# logger_SMD_0603_v1.net
KiCad netlist of a schematic drawn in EAGLE
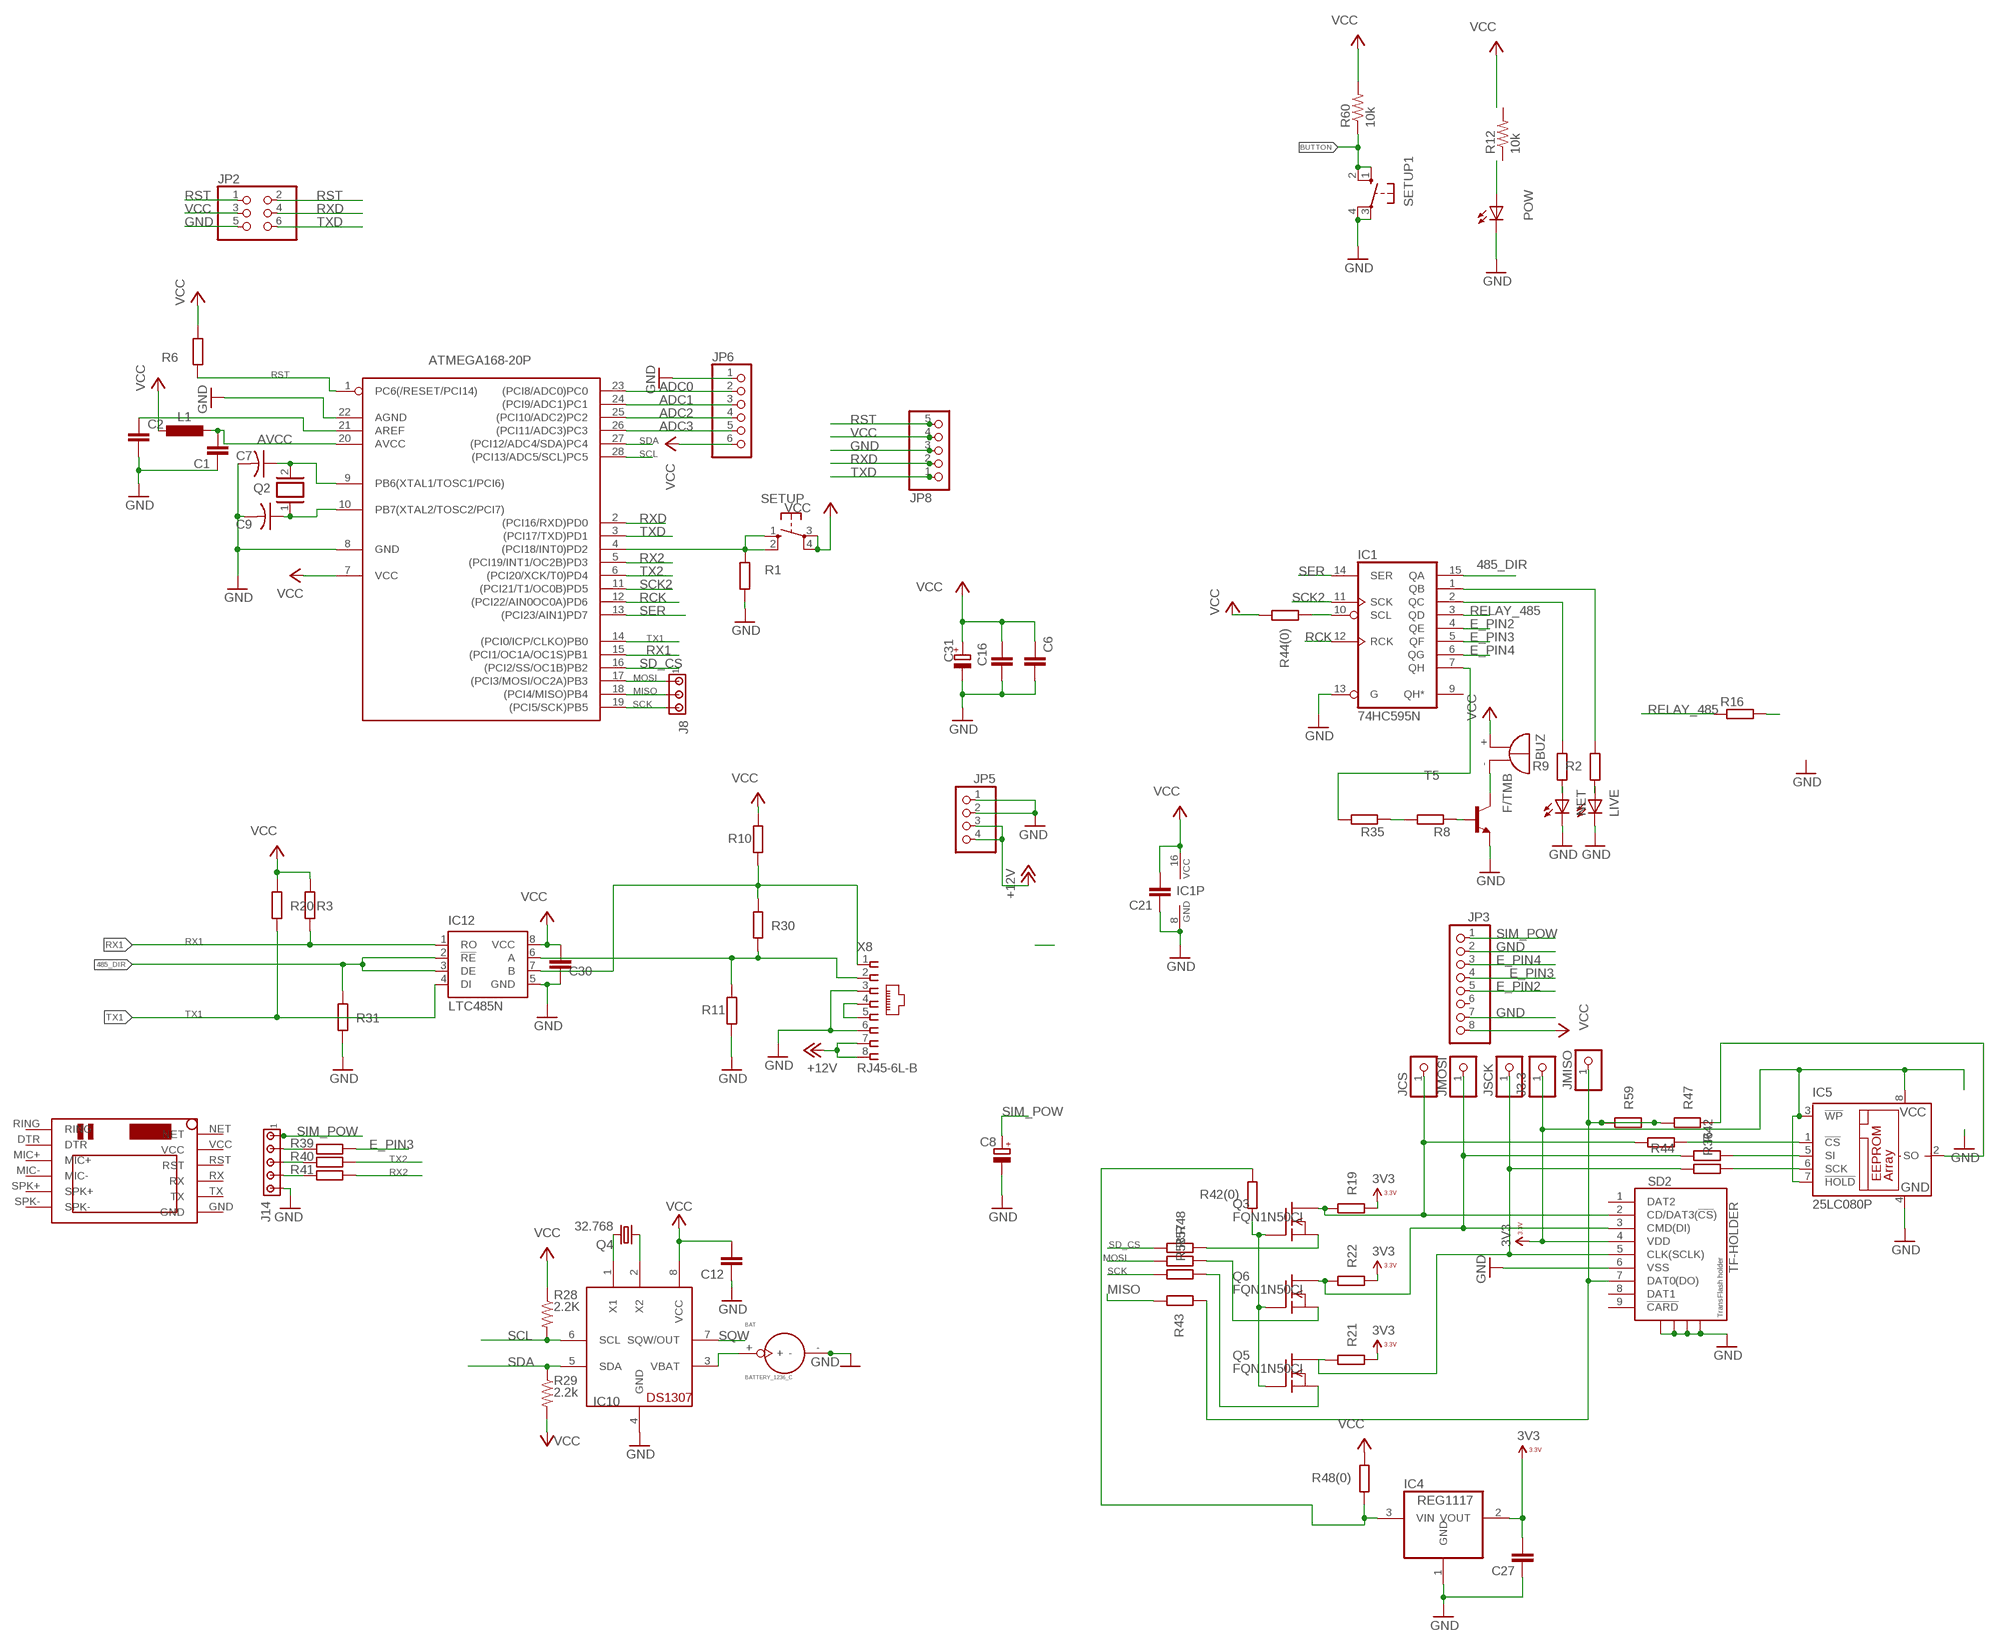
[diagram p0: schematic, sheet 1]
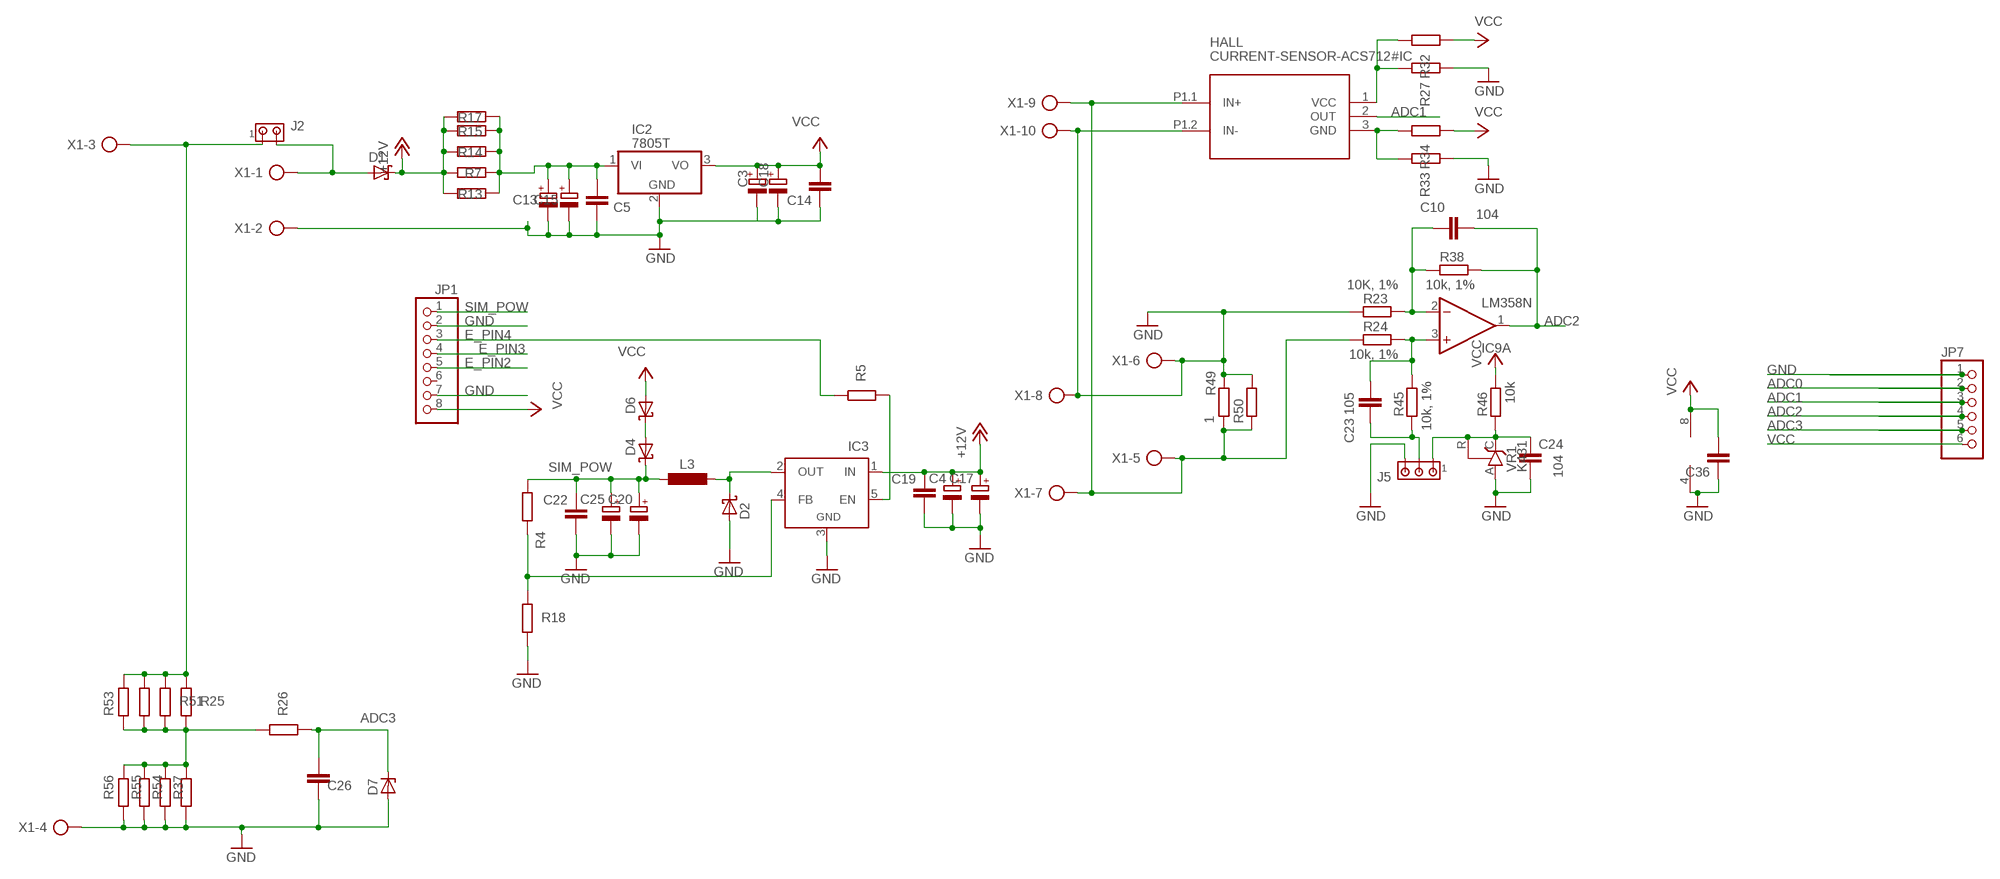
[diagram p1: schematic, sheet 2]

(export (version "E")
  (design (tool "Eeschema 10.0.6"))
  (components
    (comp (ref "BAT")
      (value "BATTERY_1236_C")
      (footprint "eagle-import:BATTERY_1236_C")
      (libsource (lib "eagle-import") (part "BATTERY_1236_C"))
    )
    (comp (ref "BUZ")
      (value "F/TMB")
      (footprint "eagle-import:F_TMB")
      (libsource (lib "eagle-import") (part "F/TMB"))
    )
    (comp (ref "C1")
      (value "C-EU050-024X044")
      (footprint "eagle-import:C050-024X044")
      (libsource (lib "eagle-import") (part "C-EU050-024X044"))
    )
    (comp (ref "C2")
      (value "C-EU025-025X050")
      (footprint "eagle-import:C025-025X050")
      (libsource (lib "eagle-import") (part "C-EU025-025X050"))
    )
    (comp (ref "C6")
      (value "C-EU025-025X050")
      (footprint "eagle-import:C025-025X050")
      (libsource (lib "eagle-import") (part "C-EU025-025X050"))
    )
    (comp (ref "C7")
      (value "C-US050-024X044")
      (footprint "eagle-import:C050-024X044")
      (libsource (lib "eagle-import") (part "C-US050-024X044"))
    )
    (comp (ref "C8")
      (value "CPOL-EUE2.5-6")
      (footprint "eagle-import:E2,5-6")
      (libsource (lib "eagle-import") (part "resistor_CPOL-EUE2.5-6"))
    )
    (comp (ref "C9")
      (value "C-US050-024X044")
      (footprint "eagle-import:C050-024X044")
      (libsource (lib "eagle-import") (part "C-US050-024X044"))
    )
    (comp (ref "C12")
      (value "C-EU075-032X103")
      (footprint "eagle-import:C075-032X103")
      (libsource (lib "eagle-import") (part "C-EU075-032X103"))
    )
    (comp (ref "C16")
      (value "C-EU050-024X044")
      (footprint "eagle-import:C050-024X044")
      (libsource (lib "eagle-import") (part "C-EU050-024X044"))
    )
    (comp (ref "C21")
      (value "C-EU050-024X044")
      (footprint "eagle-import:C050-024X044")
      (libsource (lib "eagle-import") (part "C-EU050-024X044"))
    )
    (comp (ref "C27")
      (value "C-EU050-024X044")
      (footprint "eagle-import:C050-024X044")
      (libsource (lib "eagle-import") (part "C-EU050-024X044"))
    )
    (comp (ref "C30")
      (value "C-EU050-024X044")
      (footprint "eagle-import:C050-024X044")
      (libsource (lib "eagle-import") (part "C-EU050-024X044"))
    )
    (comp (ref "C31")
      (value "CPOL-EUTT2D6")
      (footprint "eagle-import:TT2D6")
      (libsource (lib "eagle-import") (part "CPOL-EUTT2D6"))
    )
    (comp (ref "IC1")
      (value "74HC595N")
      (footprint "eagle-import:DIL16")
      (libsource (lib "eagle-import") (part "74595NHC"))
    )
    (comp (ref "IC4")
      (value "REG1117")
      (footprint "eagle-import:SOT223")
      (libsource (lib "eagle-import") (part "REG1117"))
    )
    (comp (ref "IC5")
      (value "25LC080P")
      (footprint "eagle-import:DIL8")
      (fields (field (name "MF") "MICROCHIP") (field (name "MPN") "25LC080/P"))
      (libsource (lib "eagle-import") (part "25PLC080"))
    )
    (comp (ref "IC7")
      (value "ATMEGA168-20P")
      (footprint "eagle-import:DIL28-3")
      (libsource (lib "eagle-import") (part "ATMEGA168P-20"))
    )
    (comp (ref "IC10")
      (value "DS1307")
      (footprint "eagle-import:DIL08")
      (libsource (lib "eagle-import") (part "DS1307"))
    )
    (comp (ref "IC12")
      (value "LTC485N")
      (footprint "eagle-import:DIL08")
      (libsource (lib "eagle-import") (part "LTC485N"))
    )
    (comp (ref "J3.3")
      (value "PINHD-1X1")
      (footprint "eagle-import:1X01")
      (libsource (lib "eagle-import") (part "PINHD-1X1"))
    )
    (comp (ref "J8")
      (value "MTA03-100")
      (footprint "eagle-import:10X03MTA")
      (libsource (lib "eagle-import") (part "MTA03-100"))
    )
    (comp (ref "J14")
      (value "MTA05-100")
      (footprint "eagle-import:10X05MTA")
      (libsource (lib "eagle-import") (part "MTA05-100"))
    )
    (comp (ref "JCS")
      (value "PINHD-1X1")
      (footprint "eagle-import:1X01")
      (libsource (lib "eagle-import") (part "PINHD-1X1"))
    )
    (comp (ref "JMISO")
      (value "PINHD-1X1")
      (footprint "eagle-import:1X01")
      (libsource (lib "eagle-import") (part "PINHD-1X1"))
    )
    (comp (ref "JMOSI")
      (value "PINHD-1X1")
      (footprint "eagle-import:1X01")
      (libsource (lib "eagle-import") (part "PINHD-1X1"))
    )
    (comp (ref "JP2")
      (value "PINHD-2X3")
      (footprint "eagle-import:2X03")
      (libsource (lib "eagle-import") (part "PINHD-2X3"))
    )
    (comp (ref "JP3")
      (value "PINHD-1X8")
      (footprint "eagle-import:1X08")
      (libsource (lib "eagle-import") (part "PINHD-1X8"))
    )
    (comp (ref "JP5")
      (value "PINHD-1X4")
      (footprint "eagle-import:1X04")
      (libsource (lib "eagle-import") (part "PINHD-1X4"))
    )
    (comp (ref "JP6")
      (value "PINHD-1X6")
      (footprint "eagle-import:1X06")
      (libsource (lib "eagle-import") (part "PINHD-1X6"))
    )
    (comp (ref "JP8")
      (value "PINHD-1X5/90")
      (footprint "eagle-import:1X05_90")
      (libsource (lib "eagle-import") (part "PINHD-1X5/90"))
    )
    (comp (ref "JSCK")
      (value "PINHD-1X1")
      (footprint "eagle-import:1X01")
      (libsource (lib "eagle-import") (part "PINHD-1X1"))
    )
    (comp (ref "L1")
      (value "L-EU0207/15")
      (footprint "eagle-import:0207_15")
      (libsource (lib "eagle-import") (part "L-EU0207/15"))
    )
    (comp (ref "LIVE")
      (value "LED3MM")
      (footprint "eagle-import:LED3MM")
      (libsource (lib "eagle-import") (part "LED3MM"))
    )
    (comp (ref "NET")
      (value "LED3MM")
      (footprint "eagle-import:LED3MM")
      (libsource (lib "eagle-import") (part "LED3MM"))
    )
    (comp (ref "POW")
      (value "LED3MM")
      (footprint "eagle-import:LED3MM")
      (libsource (lib "eagle-import") (part "LED3MM"))
    )
    (comp (ref "Q2")
      (value "XTAL/S")
      (footprint "eagle-import:QS")
      (libsource (lib "eagle-import") (part "XTAL/S"))
    )
    (comp (ref "Q3")
      (value "FQN1N50CI")
      (footprint "eagle-import:TO92-INLINE")
      (libsource (lib "eagle-import") (part "FQN1N50CI"))
    )
    (comp (ref "Q4")
      (value "32.768")
      (footprint "eagle-import:TC38H")
      (libsource (lib "eagle-import") (part "CRYTALTC38H"))
    )
    (comp (ref "Q5")
      (value "FQN1N50CI")
      (footprint "eagle-import:TO92-INLINE")
      (libsource (lib "eagle-import") (part "FQN1N50CI"))
    )
    (comp (ref "Q6")
      (value "FQN1N50CI")
      (footprint "eagle-import:TO92-INLINE")
      (libsource (lib "eagle-import") (part "FQN1N50CI"))
    )
    (comp (ref "R1")
      (value "R-EU_0204/7")
      (footprint "eagle-import:0204_7")
      (libsource (lib "eagle-import") (part "R-EU_0204/7"))
    )
    (comp (ref "R2")
      (value "R-EU_0207/12")
      (footprint "eagle-import:0207_12")
      (libsource (lib "eagle-import") (part "R-EU_0207/12"))
    )
    (comp (ref "R3")
      (value "R-EU_0204/7")
      (footprint "eagle-import:0204_7")
      (libsource (lib "eagle-import") (part "R-EU_0204/7"))
    )
    (comp (ref "R6")
      (value "R-EU_0204/7")
      (footprint "eagle-import:0204_7")
      (libsource (lib "eagle-import") (part "R-EU_0204/7"))
    )
    (comp (ref "R8")
      (value "R-EU_0207/10")
      (footprint "eagle-import:0207_10")
      (libsource (lib "eagle-import") (part "R-EU_0207/10"))
    )
    (comp (ref "R9")
      (value "R-EU_0207/12")
      (footprint "eagle-import:0207_12")
      (libsource (lib "eagle-import") (part "R-EU_0207/12"))
    )
    (comp (ref "R10")
      (value "R-EU_0204/7")
      (footprint "eagle-import:0204_7")
      (libsource (lib "eagle-import") (part "R-EU_0204/7"))
    )
    (comp (ref "R11")
      (value "R-EU_0204/7")
      (footprint "eagle-import:0204_7")
      (libsource (lib "eagle-import") (part "R-EU_0204/7"))
    )
    (comp (ref "R12")
      (value "10k")
      (footprint "eagle-import:R0805")
      (libsource (lib "eagle-import") (part "resistor_R-US_R0805"))
    )
    (comp (ref "R16")
      (value "R-EU_0207/10")
      (footprint "eagle-import:0207_10")
      (libsource (lib "eagle-import") (part "resistor_R-EU_0207/10"))
    )
    (comp (ref "R19")
      (value "R-EU_0204/7")
      (footprint "eagle-import:0204_7")
      (libsource (lib "eagle-import") (part "R-EU_0204/7"))
    )
    (comp (ref "R20")
      (value "R-EU_0204/7")
      (footprint "eagle-import:0204_7")
      (libsource (lib "eagle-import") (part "R-EU_0204/7"))
    )
    (comp (ref "R21")
      (value "R-EU_0204/7")
      (footprint "eagle-import:0204_7")
      (libsource (lib "eagle-import") (part "R-EU_0204/7"))
    )
    (comp (ref "R22")
      (value "R-EU_0204/7")
      (footprint "eagle-import:0204_7")
      (libsource (lib "eagle-import") (part "R-EU_0204/7"))
    )
    (comp (ref "R28")
      (value "2.2K")
      (footprint "eagle-import:0204_7")
      (libsource (lib "eagle-import") (part "R-US_0204/7"))
    )
    (comp (ref "R29")
      (value "2.2k")
      (footprint "eagle-import:0204_7")
      (libsource (lib "eagle-import") (part "R-US_0204/7"))
    )
    (comp (ref "R30")
      (value "R-EU_0204/7")
      (footprint "eagle-import:0204_7")
      (libsource (lib "eagle-import") (part "R-EU_0204/7"))
    )
    (comp (ref "R31")
      (value "R-EU_0204/7")
      (footprint "eagle-import:0204_7")
      (libsource (lib "eagle-import") (part "R-EU_0204/7"))
    )
    (comp (ref "R35")
      (value "R-EU_0204/7")
      (footprint "eagle-import:0204_7")
      (libsource (lib "eagle-import") (part "R-EU_0204/7"))
    )
    (comp (ref "R36")
      (value "R-EU_0207/10")
      (footprint "eagle-import:0207_10")
      (libsource (lib "eagle-import") (part "R-EU_0207/10"))
    )
    (comp (ref "R39")
      (value "R-EU_0207/10")
      (footprint "eagle-import:0207_10")
      (libsource (lib "eagle-import") (part "R-EU_0207/10"))
    )
    (comp (ref "R40")
      (value "R-EU_0207/12")
      (footprint "eagle-import:0207_12")
      (libsource (lib "eagle-import") (part "R-EU_0207/12"))
    )
    (comp (ref "R41")
      (value "R-EU_0207/12")
      (footprint "eagle-import:0207_12")
      (libsource (lib "eagle-import") (part "R-EU_0207/12"))
    )
    (comp (ref "R42")
      (value "R-EU_0207/10")
      (footprint "eagle-import:0207_10")
      (libsource (lib "eagle-import") (part "R-EU_0207/10"))
    )
    (comp (ref "R42(0)")
      (value "R-EU_0207/10")
      (footprint "eagle-import:0207_10")
      (libsource (lib "eagle-import") (part "R-EU_0207/10"))
    )
    (comp (ref "R43")
      (value "R-EU_0204/7")
      (footprint "eagle-import:0204_7")
      (libsource (lib "eagle-import") (part "R-EU_0204/7"))
    )
    (comp (ref "R44")
      (value "R-EU_0207/10")
      (footprint "eagle-import:0207_10")
      (libsource (lib "eagle-import") (part "R-EU_0207/10"))
    )
    (comp (ref "R44(0)")
      (value "R-EU_0207/10")
      (footprint "eagle-import:0207_10")
      (libsource (lib "eagle-import") (part "R-EU_0207/10"))
    )
    (comp (ref "R47")
      (value "R-EU_0207/10")
      (footprint "eagle-import:0207_10")
      (libsource (lib "eagle-import") (part "R-EU_0207/10"))
    )
    (comp (ref "R48")
      (value "R-EU_0204/7")
      (footprint "eagle-import:0204_7")
      (libsource (lib "eagle-import") (part "R-EU_0204/7"))
    )
    (comp (ref "R48(0)")
      (value "R-EU_0207/10")
      (footprint "eagle-import:0207_10")
      (libsource (lib "eagle-import") (part "R-EU_0207/10"))
    )
    (comp (ref "R57")
      (value "R-EU_0204/7")
      (footprint "eagle-import:0204_7")
      (libsource (lib "eagle-import") (part "R-EU_0204/7"))
    )
    (comp (ref "R58")
      (value "R-EU_0204/7")
      (footprint "eagle-import:0204_7")
      (libsource (lib "eagle-import") (part "R-EU_0204/7"))
    )
    (comp (ref "R59")
      (value "R-EU_0204/7")
      (footprint "eagle-import:0204_7")
      (libsource (lib "eagle-import") (part "R-EU_0204/7"))
    )
    (comp (ref "R60")
      (value "10k")
      (footprint "eagle-import:R0805")
      (libsource (lib "eagle-import") (part "resistor_R-US_R0805"))
    )
    (comp (ref "SD2")
      (value "TF-HOLDER")
      (footprint "eagle-import:TF-PULL")
      (libsource (lib "eagle-import") (part "TF-HOLDER"))
    )
    (comp (ref "SETUP")
      (value "10-XX")
      (footprint "eagle-import:B3F-10XX")
      (fields (field (name "MPN") "B3F-1000"))
      (libsource (lib "eagle-import") (part "10-XX"))
    )
    (comp (ref "SETUP1")
      (value "10-XX")
      (footprint "eagle-import:B3F-10XX")
      (fields (field (name "MPN") "B3F-1000"))
      (libsource (lib "eagle-import") (part "10-XX"))
    )
    (comp (ref "T5")
      (value "BC547A-NPN-TO92-CBE")
      (footprint "eagle-import:TO92-CBE")
      (libsource (lib "eagle-import") (part "-NPN-TO92-CBEBC547A"))
    )
    (comp (ref "U$1")
      (value "SIM800LMODULE")
      (footprint "eagle-import:SIM800LMODULE")
      (libsource (lib "eagle-import") (part "SIM800LMODULE"))
    )
    (comp (ref "X8")
      (value "RJ45-6L-B")
      (footprint "eagle-import:RJ45-NO-SHIELD")
      (libsource (lib "eagle-import") (part "RJ45-6L-B"))
    )
    (comp (ref "C3")
      (value "CPOL-EUTT2D6")
      (footprint "eagle-import:TT2D6")
      (libsource (lib "eagle-import") (part "CPOL-EUTT2D6"))
    )
    (comp (ref "C4")
      (value "CPOL-EUE2.5-6")
      (footprint "eagle-import:E2,5-6")
      (libsource (lib "eagle-import") (part "resistor_CPOL-EUE2.5-6"))
    )
    (comp (ref "C5")
      (value "C-EU050-024X044")
      (footprint "eagle-import:C050-024X044")
      (libsource (lib "eagle-import") (part "C-EU050-024X044"))
    )
    (comp (ref "C10")
      (value "104")
      (footprint "eagle-import:C050-024X044")
      (libsource (lib "eagle-import") (part "C-EU050-024X044"))
    )
    (comp (ref "C13")
      (value "CPOL-EUTT2D6")
      (footprint "eagle-import:TT2D6")
      (libsource (lib "eagle-import") (part "CPOL-EUTT2D6"))
    )
    (comp (ref "C14")
      (value "C-EU050-024X044")
      (footprint "eagle-import:C050-024X044")
      (libsource (lib "eagle-import") (part "C-EU050-024X044"))
    )
    (comp (ref "C15")
      (value "CPOL-EUTT2D6")
      (footprint "eagle-import:TT2D6")
      (libsource (lib "eagle-import") (part "CPOL-EUTT2D6"))
    )
    (comp (ref "C17")
      (value "CPOL-EUE2.5-6")
      (footprint "eagle-import:E2,5-6")
      (libsource (lib "eagle-import") (part "resistor_CPOL-EUE2.5-6"))
    )
    (comp (ref "C18")
      (value "CPOL-EUTT2D6")
      (footprint "eagle-import:TT2D6")
      (libsource (lib "eagle-import") (part "CPOL-EUTT2D6"))
    )
    (comp (ref "C19")
      (value "C-EU050-024X044")
      (footprint "eagle-import:C050-024X044")
      (libsource (lib "eagle-import") (part "resistor_C-EU050-024X044"))
    )
    (comp (ref "C20")
      (value "CPOL-EUE2.5-6")
      (footprint "eagle-import:E2,5-6")
      (libsource (lib "eagle-import") (part "resistor_CPOL-EUE2.5-6"))
    )
    (comp (ref "C22")
      (value "C-EU050-024X044")
      (footprint "eagle-import:C050-024X044")
      (libsource (lib "eagle-import") (part "resistor_C-EU050-024X044"))
    )
    (comp (ref "C23")
      (value "105")
      (footprint "eagle-import:C050-024X044")
      (libsource (lib "eagle-import") (part "C-EU050-024X044"))
    )
    (comp (ref "C24")
      (value "104")
      (footprint "eagle-import:C050-024X044")
      (libsource (lib "eagle-import") (part "C-EU050-024X044"))
    )
    (comp (ref "C25")
      (value "CPOL-EUE2.5-6")
      (footprint "eagle-import:E2,5-6")
      (libsource (lib "eagle-import") (part "resistor_CPOL-EUE2.5-6"))
    )
    (comp (ref "C26")
      (value "C-EU050-024X044")
      (footprint "eagle-import:C050-024X044")
      (libsource (lib "eagle-import") (part "C-EU050-024X044"))
    )
    (comp (ref "C36")
      (value "C-EU050-024X044")
      (footprint "eagle-import:C050-024X044")
      (libsource (lib "eagle-import") (part "C-EU050-024X044"))
    )
    (comp (ref "D1")
      (value "SCHOTTKY-DIODEDO41")
      (footprint "eagle-import:DO41-10")
      (libsource (lib "eagle-import") (part "SCHOTTKY-DIODEDO41"))
    )
    (comp (ref "D2")
      (value "SCHOTTKY-DIODEDO41")
      (footprint "eagle-import:DO41-10")
      (libsource (lib "eagle-import") (part "SCHOTTKY-DIODEDO41"))
    )
    (comp (ref "D4")
      (value "SCHOTTKY-DIODEDO41")
      (footprint "eagle-import:DO41-10")
      (libsource (lib "eagle-import") (part "SCHOTTKY-DIODEDO41"))
    )
    (comp (ref "D6")
      (value "SCHOTTKY-DIODEDO41")
      (footprint "eagle-import:DO41-10")
      (libsource (lib "eagle-import") (part "SCHOTTKY-DIODEDO41"))
    )
    (comp (ref "D7")
      (value "ZENER-DIODEDO35Z10")
      (footprint "eagle-import:DO35Z10")
      (libsource (lib "eagle-import") (part "ZENER-DIODEDO35Z10"))
    )
    (comp (ref "HALL")
      (value "CURRENT-SENSOR-ACS712#IC")
      (footprint "eagle-import:CURRENT-SENSOR-ACS712#IC")
      (libsource (lib "eagle-import") (part "CURRENT-SENSOR-ACS712#IC"))
    )
    (comp (ref "IC2")
      (value "7805T")
      (footprint "eagle-import:TO220H")
      (libsource (lib "eagle-import") (part "78T05"))
    )
    (comp (ref "IC3")
      (value "LM2596TH")
      (footprint "eagle-import:TO220-52")
      (libsource (lib "eagle-import") (part "LM2596TH"))
    )
    (comp (ref "IC9")
      (value "LM358N")
      (footprint "eagle-import:DIL08")
      (libsource (lib "eagle-import") (part "LM358N"))
    )
    (comp (ref "J2")
      (value "MTA02-100")
      (footprint "eagle-import:10X02MTA")
      (libsource (lib "eagle-import") (part "MTA02-100"))
    )
    (comp (ref "J5")
      (value "MTA03-100")
      (footprint "eagle-import:10X03MTA")
      (libsource (lib "eagle-import") (part "MTA03-100"))
    )
    (comp (ref "JP1")
      (value "PINHD-1X8")
      (footprint "eagle-import:1X08")
      (libsource (lib "eagle-import") (part "PINHD-1X8"))
    )
    (comp (ref "JP7")
      (value "PINHD-1X6")
      (footprint "eagle-import:1X06")
      (libsource (lib "eagle-import") (part "PINHD-1X6"))
    )
    (comp (ref "L3")
      (value "L-EU0207/10")
      (footprint "eagle-import:0207_10")
      (libsource (lib "eagle-import") (part "L-EU0207/10"))
    )
    (comp (ref "R4")
      (value "R-EU_0204/7")
      (footprint "eagle-import:0204_7")
      (libsource (lib "eagle-import") (part "R-EU_0204/7"))
    )
    (comp (ref "R5")
      (value "R-EU_0207/12")
      (footprint "eagle-import:0207_12")
      (libsource (lib "eagle-import") (part "R-EU_0207/12"))
    )
    (comp (ref "R7")
      (value "R-EU_0204/7")
      (footprint "eagle-import:0204_7")
      (libsource (lib "eagle-import") (part "R-EU_0204/7"))
    )
    (comp (ref "R13")
      (value "R-EU_0204/7")
      (footprint "eagle-import:0204_7")
      (libsource (lib "eagle-import") (part "R-EU_0204/7"))
    )
    (comp (ref "R14")
      (value "R-EU_0204/7")
      (footprint "eagle-import:0204_7")
      (libsource (lib "eagle-import") (part "R-EU_0204/7"))
    )
    (comp (ref "R15")
      (value "R-EU_0204/7")
      (footprint "eagle-import:0204_7")
      (libsource (lib "eagle-import") (part "R-EU_0204/7"))
    )
    (comp (ref "R17")
      (value "R-EU_0204/7")
      (footprint "eagle-import:0204_7")
      (libsource (lib "eagle-import") (part "R-EU_0204/7"))
    )
    (comp (ref "R18")
      (value "R-EU_0204/7")
      (footprint "eagle-import:0204_7")
      (libsource (lib "eagle-import") (part "R-EU_0204/7"))
    )
    (comp (ref "R23")
      (value "10K, 1%")
      (footprint "eagle-import:0204_7")
      (libsource (lib "eagle-import") (part "R-EU_0204/7"))
    )
    (comp (ref "R24")
      (value "10k, 1%")
      (footprint "eagle-import:0204_7")
      (libsource (lib "eagle-import") (part "R-EU_0204/7"))
    )
    (comp (ref "R25")
      (value "R-EU_0204/7")
      (footprint "eagle-import:0204_7")
      (libsource (lib "eagle-import") (part "R-EU_0204/7"))
    )
    (comp (ref "R26")
      (value "R-EU_0204/7")
      (footprint "eagle-import:0204_7")
      (libsource (lib "eagle-import") (part "R-EU_0204/7"))
    )
    (comp (ref "R27")
      (value "R-EU_0204/7")
      (footprint "eagle-import:0204_7")
      (libsource (lib "eagle-import") (part "R-EU_0204/7"))
    )
    (comp (ref "R32")
      (value "R-EU_0204/7")
      (footprint "eagle-import:0204_7")
      (libsource (lib "eagle-import") (part "R-EU_0204/7"))
    )
    (comp (ref "R33")
      (value "R-EU_0204/7")
      (footprint "eagle-import:0204_7")
      (libsource (lib "eagle-import") (part "R-EU_0204/7"))
    )
    (comp (ref "R34")
      (value "R-EU_0204/7")
      (footprint "eagle-import:0204_7")
      (libsource (lib "eagle-import") (part "R-EU_0204/7"))
    )
    (comp (ref "R37")
      (value "R-EU_0204/7")
      (footprint "eagle-import:0204_7")
      (libsource (lib "eagle-import") (part "R-EU_0204/7"))
    )
    (comp (ref "R38")
      (value "10k, 1%")
      (footprint "eagle-import:0204_7")
      (libsource (lib "eagle-import") (part "R-EU_0204/7"))
    )
    (comp (ref "R45")
      (value "10k, 1%")
      (footprint "eagle-import:0204_7")
      (libsource (lib "eagle-import") (part "R-EU_0204/7"))
    )
    (comp (ref "R46")
      (value "10k")
      (footprint "eagle-import:0207_12")
      (libsource (lib "eagle-import") (part "R-EU_0207/12"))
    )
    (comp (ref "R49")
      (value "1")
      (footprint "eagle-import:MINI_MELF-0207R")
      (libsource (lib "eagle-import") (part "resistor_R-EU_MELF0207R"))
    )
    (comp (ref "R50")
      (value "R-EU_MELF0207R")
      (footprint "eagle-import:MINI_MELF-0207R")
      (libsource (lib "eagle-import") (part "resistor_R-EU_MELF0207R"))
    )
    (comp (ref "R51")
      (value "R-EU_0204/7")
      (footprint "eagle-import:0204_7")
      (libsource (lib "eagle-import") (part "R-EU_0204/7"))
    )
    (comp (ref "R52")
      (value "R-EU_0204/7")
      (footprint "eagle-import:0204_7")
      (libsource (lib "eagle-import") (part "R-EU_0204/7"))
    )
    (comp (ref "R53")
      (value "R-EU_0204/7")
      (footprint "eagle-import:0204_7")
      (libsource (lib "eagle-import") (part "R-EU_0204/7"))
    )
    (comp (ref "R54")
      (value "R-EU_0204/7")
      (footprint "eagle-import:0204_7")
      (libsource (lib "eagle-import") (part "R-EU_0204/7"))
    )
    (comp (ref "R55")
      (value "R-EU_0204/7")
      (footprint "eagle-import:0204_7")
      (libsource (lib "eagle-import") (part "R-EU_0204/7"))
    )
    (comp (ref "R56")
      (value "R-EU_0204/7")
      (footprint "eagle-import:0204_7")
      (libsource (lib "eagle-import") (part "R-EU_0204/7"))
    )
    (comp (ref "VR1")
      (value "K431")
      (footprint "eagle-import:TO92-CLP")
      (libsource (lib "eagle-import") (part "TL431CLP"))
    )
    (comp (ref "X1")
      (value "AK500/10")
      (footprint "eagle-import:AK500_10")
      (libsource (lib "eagle-import") (part "AK500/10"))
    )
  )
  (nets
    (net (code "1") (name "+12V") (class "Default")
      (node (ref "C17") (pin "+") (pinfunction "+_+") (pintype "passive"))
      (node (ref "C19") (pin "1") (pinfunction "1_1") (pintype "passive"))
      (node (ref "C4") (pin "+") (pinfunction "+_+") (pintype "passive"))
      (node (ref "D1") (pin "C") (pinfunction "C_C") (pintype "passive"))
      (node (ref "IC3") (pin "1") (pinfunction "IN_1") (pintype "input"))
      (node (ref "JP5") (pin "3") (pinfunction "3_3") (pintype "passive"))
      (node (ref "JP5") (pin "4") (pinfunction "4_4") (pintype "passive"))
      (node (ref "R13") (pin "2") (pinfunction "2_2") (pintype "passive"))
      (node (ref "R14") (pin "2") (pinfunction "2_2") (pintype "passive"))
      (node (ref "R15") (pin "2") (pinfunction "2_2") (pintype "passive"))
      (node (ref "R17") (pin "2") (pinfunction "2_2") (pintype "passive"))
      (node (ref "R7") (pin "2") (pinfunction "2_2") (pintype "passive"))
      (node (ref "X8") (pin "7") (pinfunction "7_7") (pintype "passive"))
      (node (ref "X8") (pin "8") (pinfunction "8_8") (pintype "passive"))
    )
    (net (code "2") (name "3V3") (class "Default")
      (node (ref "C27") (pin "2") (pinfunction "2_2") (pintype "passive"))
      (node (ref "IC4") (pin "2") (pinfunction "VOUT_2") (pintype "output"))
      (node (ref "IC5") (pin "3") (pinfunction "~{WP}_3") (pintype "input"))
      (node (ref "IC5") (pin "7") (pinfunction "~{HOLD}_7") (pintype "input"))
      (node (ref "IC5") (pin "8") (pinfunction "VCC_8") (pintype "power_in"))
      (node (ref "J3.3") (pin "1") (pinfunction "1_1") (pintype "passive"))
      (node (ref "R19") (pin "2") (pinfunction "2_2") (pintype "passive"))
      (node (ref "R21") (pin "2") (pinfunction "2_2") (pintype "passive"))
      (node (ref "R22") (pin "2") (pinfunction "2_2") (pintype "passive"))
      (node (ref "SD2") (pin "4") (pinfunction "VDD_4") (pintype "power_in"))
    )
    (net (code "3") (name "485_DIR") (class "Default")
      (node (ref "IC1") (pin "15") (pinfunction "QA_15") (pintype "tri_state"))
      (node (ref "IC12") (pin "2") (pinfunction "~{RE}_2") (pintype "input"))
      (node (ref "IC12") (pin "3") (pinfunction "DE_3") (pintype "input"))
      (node (ref "R31") (pin "1") (pinfunction "1_1") (pintype "passive"))
    )
    (net (code "4") (name "ADC0") (class "Default")
      (node (ref "IC7") (pin "23") (pinfunction "(PCI8/ADC0)PC0_23") (pintype "bidirectional"))
      (node (ref "JP6") (pin "2") (pinfunction "2_2") (pintype "passive"))
      (node (ref "JP7") (pin "2") (pinfunction "2_2") (pintype "passive"))
    )
    (net (code "5") (name "ADC1") (class "Default")
      (node (ref "HALL") (pin "2") (pinfunction "OUT_2") (pintype "output"))
      (node (ref "IC7") (pin "24") (pinfunction "(PCI9/ADC1)PC1_24") (pintype "bidirectional"))
      (node (ref "JP6") (pin "3") (pinfunction "3_3") (pintype "passive"))
      (node (ref "JP7") (pin "3") (pinfunction "3_3") (pintype "passive"))
    )
    (net (code "6") (name "ADC2") (class "Default")
      (node (ref "C10") (pin "1") (pinfunction "1_1") (pintype "passive"))
      (node (ref "IC7") (pin "25") (pinfunction "(PCI10/ADC2)PC2_25") (pintype "bidirectional"))
      (node (ref "IC9") (pin "1") (pinfunction "OUT_1") (pintype "output"))
      (node (ref "JP6") (pin "4") (pinfunction "4_4") (pintype "passive"))
      (node (ref "JP7") (pin "4") (pinfunction "4_4") (pintype "passive"))
      (node (ref "R38") (pin "1") (pinfunction "1_1") (pintype "passive"))
    )
    (net (code "7") (name "ADC3") (class "Default")
      (node (ref "C26") (pin "2") (pinfunction "2_2") (pintype "passive"))
      (node (ref "D7") (pin "C") (pinfunction "C_C") (pintype "passive"))
      (node (ref "IC7") (pin "26") (pinfunction "(PCI11/ADC3)PC3_26") (pintype "bidirectional"))
      (node (ref "JP6") (pin "5") (pinfunction "5_5") (pintype "passive"))
      (node (ref "JP7") (pin "5") (pinfunction "5_5") (pintype "passive"))
      (node (ref "R26") (pin "1") (pinfunction "1_1") (pintype "passive"))
    )
    (net (code "8") (name "AVCC") (class "Default")
      (node (ref "C1") (pin "2") (pinfunction "2_2") (pintype "passive"))
      (node (ref "IC7") (pin "20") (pinfunction "AVCC_20") (pintype "bidirectional"))
      (node (ref "L1") (pin "2") (pinfunction "2_2") (pintype "passive"))
    )
    (net (code "9") (name "BUTTON") (class "Default")
      (node (ref "R60") (pin "1") (pinfunction "1_1") (pintype "passive"))
      (node (ref "SETUP1") (pin "1") (pinfunction "S_1") (pintype "passive"))
      (node (ref "SETUP1") (pin "2") (pinfunction "S1_2") (pintype "passive"))
    )
    (net (code "10") (name "E_PIN2") (class "Default")
      (node (ref "IC1") (pin "4") (pinfunction "QE_4") (pintype "tri_state"))
      (node (ref "JP1") (pin "5") (pinfunction "5_5") (pintype "passive"))
      (node (ref "JP3") (pin "5") (pinfunction "5_5") (pintype "passive"))
    )
    (net (code "11") (name "E_PIN3") (class "Default")
      (node (ref "IC1") (pin "5") (pinfunction "QF_5") (pintype "tri_state"))
      (node (ref "JP1") (pin "4") (pinfunction "4_4") (pintype "passive"))
      (node (ref "JP3") (pin "4") (pinfunction "4_4") (pintype "passive"))
      (node (ref "R39") (pin "1") (pinfunction "1_1") (pintype "passive"))
    )
    (net (code "12") (name "E_PIN4") (class "Default")
      (node (ref "IC1") (pin "6") (pinfunction "QG_6") (pintype "tri_state"))
      (node (ref "JP1") (pin "3") (pinfunction "3_3") (pintype "passive"))
      (node (ref "JP3") (pin "3") (pinfunction "3_3") (pintype "passive"))
      (node (ref "R5") (pin "2") (pinfunction "2_2") (pintype "passive"))
    )
    (net (code "13") (name "GND") (class "Default")
      (node (ref "BAT") (pin "-") (pinfunction "-_-") (pintype "bidirectional"))
      (node (ref "C1") (pin "1") (pinfunction "1_1") (pintype "passive"))
      (node (ref "C12") (pin "1") (pinfunction "1_1") (pintype "passive"))
      (node (ref "C13") (pin "-") (pinfunction "-_-") (pintype "passive"))
      (node (ref "C14") (pin "1") (pinfunction "1_1") (pintype "passive"))
      (node (ref "C15") (pin "-") (pinfunction "-_-") (pintype "passive"))
      (node (ref "C16") (pin "1") (pinfunction "1_1") (pintype "passive"))
      (node (ref "C17") (pin "-") (pinfunction "-_-") (pintype "passive"))
      (node (ref "C18") (pin "-") (pinfunction "-_-") (pintype "passive"))
      (node (ref "C19") (pin "2") (pinfunction "2_2") (pintype "passive"))
      (node (ref "C2") (pin "1") (pinfunction "1_1") (pintype "passive"))
      (node (ref "C20") (pin "-") (pinfunction "-_-") (pintype "passive"))
      (node (ref "C21") (pin "1") (pinfunction "1_1") (pintype "passive"))
      (node (ref "C22") (pin "2") (pinfunction "2_2") (pintype "passive"))
      (node (ref "C24") (pin "2") (pinfunction "2_2") (pintype "passive"))
      (node (ref "C25") (pin "-") (pinfunction "-_-") (pintype "passive"))
      (node (ref "C26") (pin "1") (pinfunction "1_1") (pintype "passive"))
      (node (ref "C27") (pin "1") (pinfunction "1_1") (pintype "passive"))
      (node (ref "C3") (pin "-") (pinfunction "-_-") (pintype "passive"))
      (node (ref "C30") (pin "1") (pinfunction "1_1") (pintype "passive"))
      (node (ref "C31") (pin "-") (pinfunction "-_-") (pintype "passive"))
      (node (ref "C36") (pin "1") (pinfunction "1_1") (pintype "passive"))
      (node (ref "C4") (pin "-") (pinfunction "-_-") (pintype "passive"))
      (node (ref "C5") (pin "1") (pinfunction "1_1") (pintype "passive"))
      (node (ref "C6") (pin "1") (pinfunction "1_1") (pintype "passive"))
      (node (ref "C7") (pin "2") (pinfunction "2_2") (pintype "passive"))
      (node (ref "C8") (pin "-") (pinfunction "-_-") (pintype "passive"))
      (node (ref "C9") (pin "2") (pinfunction "2_2") (pintype "passive"))
      (node (ref "D2") (pin "A") (pinfunction "A_A") (pintype "passive"))
      (node (ref "D7") (pin "A") (pinfunction "A_A") (pintype "passive"))
      (node (ref "HALL") (pin "P1.2") (pinfunction "IN-_P1.2") (pintype "bidirectional"))
      (node (ref "IC1") (pin "13") (pinfunction "G_13") (pintype "input"))
      (node (ref "IC1") (pin "8") (pinfunction "GND_8") (pintype "power_in"))
      (node (ref "IC10") (pin "4") (pinfunction "GND_4") (pintype "power_in"))
      (node (ref "IC12") (pin "5") (pinfunction "GND_5") (pintype "input"))
      (node (ref "IC2") (pin "2") (pinfunction "GND_2") (pintype "passive"))
      (node (ref "IC3") (pin "3") (pinfunction "GND_3") (pintype "power_in"))
      (node (ref "IC4") (pin "1") (pinfunction "GND_1") (pintype "power_in"))
      (node (ref "IC5") (pin "4") (pinfunction "GND_4") (pintype "power_in"))
      (node (ref "IC7") (pin "22") (pinfunction "AGND_22") (pintype "bidirectional"))
      (node (ref "IC7") (pin "8") (pinfunction "GND_8") (pintype "bidirectional"))
      (node (ref "IC9") (pin "4") (pinfunction "V-_4") (pintype "power_in"))
      (node (ref "J14") (pin "5") (pinfunction "5_5") (pintype "passive"))
      (node (ref "J5") (pin "3") (pinfunction "3_3") (pintype "passive"))
      (node (ref "JP1") (pin "2") (pinfunction "2_2") (pintype "passive"))
      (node (ref "JP1") (pin "7") (pinfunction "7_7") (pintype "passive"))
      (node (ref "JP2") (pin "5") (pinfunction "5_5") (pintype "passive"))
      (node (ref "JP3") (pin "2") (pinfunction "2_2") (pintype "passive"))
      (node (ref "JP3") (pin "7") (pinfunction "7_7") (pintype "passive"))
      (node (ref "JP5") (pin "1") (pinfunction "1_1") (pintype "passive"))
      (node (ref "JP5") (pin "2") (pinfunction "2_2") (pintype "passive"))
      (node (ref "JP6") (pin "1") (pinfunction "1_1") (pintype "passive"))
      (node (ref "JP7") (pin "1") (pinfunction "1_1") (pintype "passive"))
      (node (ref "JP8") (pin "3") (pinfunction "3_3") (pintype "passive"))
      (node (ref "LIVE") (pin "K") (pinfunction "C_K") (pintype "passive"))
      (node (ref "NET") (pin "K") (pinfunction "C_K") (pintype "passive"))
      (node (ref "POW") (pin "K") (pinfunction "C_K") (pintype "passive"))
      (node (ref "R1") (pin "2") (pinfunction "2_2") (pintype "passive"))
      (node (ref "R11") (pin "1") (pinfunction "1_1") (pintype "passive"))
      (node (ref "R18") (pin "1") (pinfunction "1_1") (pintype "passive"))
      (node (ref "R23") (pin "2") (pinfunction "2_2") (pintype "passive"))
      (node (ref "R27") (pin "1") (pinfunction "1_1") (pintype "passive"))
      (node (ref "R31") (pin "2") (pinfunction "2_2") (pintype "passive"))
      (node (ref "R33") (pin "1") (pinfunction "1_1") (pintype "passive"))
      (node (ref "R37") (pin "1") (pinfunction "1_1") (pintype "passive"))
      (node (ref "R49") (pin "2") (pinfunction "2_2") (pintype "passive"))
      (node (ref "R50") (pin "2") (pinfunction "2_2") (pintype "passive"))
      (node (ref "R54") (pin "1") (pinfunction "1_1") (pintype "passive"))
      (node (ref "R55") (pin "1") (pinfunction "1_1") (pintype "passive"))
      (node (ref "R56") (pin "1") (pinfunction "1_1") (pintype "passive"))
      (node (ref "SD2") (pin "6") (pinfunction "VSS_6") (pintype "power_in"))
      (node (ref "SD2") (pin "S1") (pinfunction "S1_S1") (pintype "passive"))
      (node (ref "SD2") (pin "S2") (pinfunction "S2_S2") (pintype "passive"))
      (node (ref "SD2") (pin "S3") (pinfunction "S3_S3") (pintype "passive"))
      (node (ref "SD2") (pin "S4") (pinfunction "S4_S4") (pintype "passive"))
      (node (ref "SETUP1") (pin "3") (pinfunction "P_3") (pintype "passive"))
      (node (ref "SETUP1") (pin "4") (pinfunction "P1_4") (pintype "passive"))
      (node (ref "T5") (pin "E") (pinfunction "E_E") (pintype "passive"))
      (node (ref "VR1") (pin "A") (pinfunction "A_A") (pintype "passive"))
      (node (ref "X1") (pin "10") (pinfunction "KL_10") (pintype "passive"))
      (node (ref "X1") (pin "2") (pinfunction "KL_2") (pintype "passive"))
      (node (ref "X1") (pin "4") (pinfunction "KL_4") (pintype "passive"))
      (node (ref "X1") (pin "6") (pinfunction "KL_6") (pintype "passive"))
      (node (ref "X1") (pin "8") (pinfunction "KL_8") (pintype "passive"))
      (node (ref "X8") (pin "3") (pinfunction "3_3") (pintype "passive"))
      (node (ref "X8") (pin "6") (pinfunction "6_6") (pintype "passive"))
    )
    (net (code "14") (name "MISO") (class "Default")
      (node (ref "IC7") (pin "18") (pinfunction "(PCI4/MISO)PB4_18") (pintype "bidirectional"))
      (node (ref "J8") (pin "2") (pinfunction "2_2") (pintype "passive"))
      (node (ref "R43") (pin "2") (pinfunction "2_2") (pintype "passive"))
    )
    (net (code "15") (name "MOSI") (class "Default")
      (node (ref "IC7") (pin "17") (pinfunction "(PCI3/MOSI/OC2A)PB3_17") (pintype "bidirectional"))
      (node (ref "J8") (pin "1") (pinfunction "1_1") (pintype "passive"))
      (node (ref "Q6") (pin "3") (pinfunction "S_3") (pintype "passive"))
      (node (ref "R57") (pin "1") (pinfunction "1_1") (pintype "passive"))
      (node (ref "R57") (pin "2") (pinfunction "2_2") (pintype "passive"))
    )
    (net (code "16") (name "Net-(BUZ-Pad-)") (class "Default")
      (node (ref "BUZ") (pin "-") (pinfunction "-_-") (pintype "passive"))
      (node (ref "T5") (pin "C") (pinfunction "C_C") (pintype "passive"))
    )
    (net (code "17") (name "Net-(C23-Pad2)") (class "Default")
      (node (ref "C23") (pin "2") (pinfunction "2_2") (pintype "passive"))
      (node (ref "J5") (pin "2") (pinfunction "2_2") (pintype "passive"))
      (node (ref "R45") (pin "2") (pinfunction "2_2") (pintype "passive"))
    )
    (net (code "18") (name "Net-(C24-Pad1)") (class "Default")
      (node (ref "C24") (pin "1") (pinfunction "1_1") (pintype "passive"))
      (node (ref "J5") (pin "1") (pinfunction "1_1") (pintype "passive"))
      (node (ref "R46") (pin "2") (pinfunction "2_2") (pintype "passive"))
      (node (ref "VR1") (pin "C") (pinfunction "C_C") (pintype "passive"))
      (node (ref "VR1") (pin "R") (pinfunction "R_R") (pintype "passive"))
    )
    (net (code "19") (name "Net-(D4-PadA)") (class "Default")
      (node (ref "D4") (pin "A") (pinfunction "A_A") (pintype "passive"))
      (node (ref "D6") (pin "C") (pinfunction "C_C") (pintype "passive"))
    )
    (net (code "20") (name "Net-(HALL-GND)") (class "Default")
      (node (ref "HALL") (pin "3") (pinfunction "GND_3") (pintype "power_in"))
      (node (ref "R33") (pin "2") (pinfunction "2_2") (pintype "passive"))
      (node (ref "R34") (pin "2") (pinfunction "2_2") (pintype "passive"))
    )
    (net (code "21") (name "Net-(HALL-IN+)") (class "Default")
      (node (ref "HALL") (pin "P1.1") (pinfunction "IN+_P1.1") (pintype "bidirectional"))
      (node (ref "R24") (pin "2") (pinfunction "2_2") (pintype "passive"))
      (node (ref "R49") (pin "1") (pinfunction "1_1") (pintype "passive"))
      (node (ref "R50") (pin "1") (pinfunction "1_1") (pintype "passive"))
      (node (ref "X1") (pin "5") (pinfunction "KL_5") (pintype "passive"))
      (node (ref "X1") (pin "7") (pinfunction "KL_7") (pintype "passive"))
      (node (ref "X1") (pin "9") (pinfunction "KL_9") (pintype "passive"))
    )
    (net (code "22") (name "Net-(HALL-VCC)") (class "Default")
      (node (ref "HALL") (pin "1") (pinfunction "VCC_1") (pintype "power_in"))
      (node (ref "R27") (pin "2") (pinfunction "2_2") (pintype "passive"))
      (node (ref "R32") (pin "2") (pinfunction "2_2") (pintype "passive"))
    )
    (net (code "23") (name "Net-(IC1A-QB)") (class "Default")
      (node (ref "IC1") (pin "1") (pinfunction "QB_1") (pintype "tri_state"))
      (node (ref "R2") (pin "2") (pinfunction "2_2") (pintype "passive"))
    )
    (net (code "24") (name "Net-(IC1A-QC)") (class "Default")
      (node (ref "IC1") (pin "2") (pinfunction "QC_2") (pintype "tri_state"))
      (node (ref "R9") (pin "2") (pinfunction "2_2") (pintype "passive"))
    )
    (net (code "25") (name "Net-(IC1A-QH)") (class "Default")
      (node (ref "IC1") (pin "7") (pinfunction "QH_7") (pintype "tri_state"))
      (node (ref "R35") (pin "2") (pinfunction "2_2") (pintype "passive"))
    )
    (net (code "26") (name "Net-(IC1A-SCL)") (class "Default")
      (node (ref "IC1") (pin "10") (pinfunction "SCL_10") (pintype "input"))
      (node (ref "R44(0)") (pin "1") (pinfunction "1_1") (pintype "passive"))
    )
    (net (code "27") (name "Net-(IC2-VI)") (class "Default")
      (node (ref "C13") (pin "+") (pinfunction "+_+") (pintype "passive"))
      (node (ref "C15") (pin "+") (pinfunction "+_+") (pintype "passive"))
      (node (ref "C5") (pin "2") (pinfunction "2_2") (pintype "passive"))
      (node (ref "IC2") (pin "1") (pinfunction "VI_1") (pintype "input"))
      (node (ref "R13") (pin "1") (pinfunction "1_1") (pintype "passive"))
      (node (ref "R14") (pin "1") (pinfunction "1_1") (pintype "passive"))
      (node (ref "R15") (pin "1") (pinfunction "1_1") (pintype "passive"))
      (node (ref "R17") (pin "1") (pinfunction "1_1") (pintype "passive"))
      (node (ref "R7") (pin "1") (pinfunction "1_1") (pintype "passive"))
    )
    (net (code "28") (name "Net-(IC3-EN)") (class "Default")
      (node (ref "IC3") (pin "5") (pinfunction "EN_5") (pintype "input"))
      (node (ref "R5") (pin "1") (pinfunction "1_1") (pintype "passive"))
    )
    (net (code "29") (name "Net-(IC3-FB)") (class "Default")
      (node (ref "IC3") (pin "4") (pinfunction "FB_4") (pintype "input"))
      (node (ref "R18") (pin "2") (pinfunction "2_2") (pintype "passive"))
      (node (ref "R4") (pin "1") (pinfunction "1_1") (pintype "passive"))
    )
    (net (code "30") (name "Net-(IC3-OUT)") (class "Default")
      (node (ref "D2") (pin "C") (pinfunction "C_C") (pintype "passive"))
      (node (ref "IC3") (pin "2") (pinfunction "OUT_2") (pintype "output"))
      (node (ref "L3") (pin "2") (pinfunction "2_2") (pintype "passive"))
    )
    (net (code "31") (name "Net-(IC4-VIN)") (class "Default")
      (node (ref "IC4") (pin "3") (pinfunction "VIN_3") (pintype "input"))
      (node (ref "R42(0)") (pin "2") (pinfunction "2_2") (pintype "passive"))
      (node (ref "R48(0)") (pin "1") (pinfunction "1_1") (pintype "passive"))
    )
    (net (code "32") (name "Net-(IC5-SCK)") (class "Default")
      (node (ref "IC5") (pin "6") (pinfunction "SCK_6") (pintype "input"))
      (node (ref "R36") (pin "2") (pinfunction "2_2") (pintype "passive"))
    )
    (net (code "33") (name "Net-(IC5-SI)") (class "Default")
      (node (ref "IC5") (pin "5") (pinfunction "SI_5") (pintype "input"))
      (node (ref "R42") (pin "2") (pinfunction "2_2") (pintype "passive"))
    )
    (net (code "34") (name "Net-(IC5-SO)") (class "Default")
      (node (ref "IC5") (pin "2") (pinfunction "SO_2") (pintype "bidirectional"))
      (node (ref "R47") (pin "2") (pinfunction "2_2") (pintype "passive"))
    )
    (net (code "35") (name "Net-(IC5-~{CS})") (class "Default")
      (node (ref "IC5") (pin "1") (pinfunction "~{CS}_1") (pintype "input"))
      (node (ref "R44") (pin "2") (pinfunction "2_2") (pintype "passive"))
    )
    (net (code "36") (name "Net-(IC7-(PCI18{slash}INT0)PD2)") (class "Default")
      (node (ref "IC7") (pin "4") (pinfunction "(PCI18/INT0)PD2_4") (pintype "bidirectional"))
      (node (ref "R1") (pin "1") (pinfunction "1_1") (pintype "passive"))
      (node (ref "SETUP") (pin "1") (pinfunction "S_1") (pintype "passive"))
      (node (ref "SETUP") (pin "2") (pinfunction "S1_2") (pintype "passive"))
    )
    (net (code "37") (name "Net-(IC7-AREF)") (class "Default")
      (node (ref "C2") (pin "2") (pinfunction "2_2") (pintype "passive"))
      (node (ref "IC7") (pin "21") (pinfunction "AREF_21") (pintype "bidirectional"))
    )
    (net (code "38") (name "Net-(IC7-PB6(XTAL1{slash}TOSC1{slash}PCI6))") (class "Default")
      (node (ref "C7") (pin "1") (pinfunction "1_1") (pintype "passive"))
      (node (ref "IC7") (pin "9") (pinfunction "PB6(XTAL1/TOSC1/PCI6)_9") (pintype "bidirectional"))
      (node (ref "Q2") (pin "2") (pinfunction "2_2") (pintype "passive"))
    )
    (net (code "39") (name "Net-(IC7-PB7(XTAL2{slash}TOSC2{slash}PCI7))") (class "Default")
      (node (ref "C9") (pin "1") (pinfunction "1_1") (pintype "passive"))
      (node (ref "IC7") (pin "10") (pinfunction "PB7(XTAL2/TOSC2/PCI7)_10") (pintype "bidirectional"))
      (node (ref "Q2") (pin "1") (pinfunction "1_1") (pintype "passive"))
    )
    (net (code "40") (name "Net-(IC9A-+IN)") (class "Default")
      (node (ref "C23") (pin "1") (pinfunction "1_1") (pintype "passive"))
      (node (ref "IC9") (pin "3") (pinfunction "+IN_3") (pintype "input"))
      (node (ref "R24") (pin "1") (pinfunction "1_1") (pintype "passive"))
      (node (ref "R45") (pin "1") (pinfunction "1_1") (pintype "passive"))
    )
    (net (code "41") (name "Net-(IC9A--IN)") (class "Default")
      (node (ref "C10") (pin "2") (pinfunction "2_2") (pintype "passive"))
      (node (ref "IC9") (pin "2") (pinfunction "-IN_2") (pintype "input"))
      (node (ref "R23") (pin "1") (pinfunction "1_1") (pintype "passive"))
      (node (ref "R38") (pin "2") (pinfunction "2_2") (pintype "passive"))
    )
    (net (code "42") (name "Net-(IC10-VBAT)") (class "Default")
      (node (ref "BAT") (pin "+") (pinfunction "+_+") (pintype "bidirectional"))
      (node (ref "IC10") (pin "3") (pinfunction "VBAT_3") (pintype "power_in"))
    )
    (net (code "43") (name "Net-(IC10-X1)") (class "Default")
      (node (ref "IC10") (pin "1") (pinfunction "X1_1") (pintype "passive"))
      (node (ref "Q4") (pin "2") (pinfunction "2_2") (pintype "passive"))
    )
    (net (code "44") (name "Net-(IC10-X2)") (class "Default")
      (node (ref "IC10") (pin "2") (pinfunction "X2_2") (pintype "passive"))
      (node (ref "Q4") (pin "1") (pinfunction "1_1") (pintype "passive"))
    )
    (net (code "45") (name "Net-(IC12-A)") (class "Default")
      (node (ref "IC12") (pin "6") (pinfunction "A_6") (pintype "bidirectional"))
      (node (ref "R11") (pin "2") (pinfunction "2_2") (pintype "passive"))
      (node (ref "R30") (pin "2") (pinfunction "2_2") (pintype "passive"))
      (node (ref "X8") (pin "2") (pinfunction "2_2") (pintype "passive"))
    )
    (net (code "46") (name "Net-(IC12-B)") (class "Default")
      (node (ref "IC12") (pin "7") (pinfunction "B_7") (pintype "bidirectional"))
      (node (ref "R10") (pin "1") (pinfunction "1_1") (pintype "passive"))
      (node (ref "R30") (pin "1") (pinfunction "1_1") (pintype "passive"))
      (node (ref "X8") (pin "1") (pinfunction "1_1") (pintype "passive"))
    )
    (net (code "47") (name "Net-(J14-Pad2)") (class "Default")
      (node (ref "J14") (pin "2") (pinfunction "2_2") (pintype "passive"))
      (node (ref "R39") (pin "2") (pinfunction "2_2") (pintype "passive"))
    )
    (net (code "48") (name "Net-(J14-Pad3)") (class "Default")
      (node (ref "J14") (pin "3") (pinfunction "3_3") (pintype "passive"))
      (node (ref "R40") (pin "2") (pinfunction "2_2") (pintype "passive"))
    )
    (net (code "49") (name "Net-(J14-Pad4)") (class "Default")
      (node (ref "J14") (pin "4") (pinfunction "4_4") (pintype "passive"))
      (node (ref "R41") (pin "2") (pinfunction "2_2") (pintype "passive"))
    )
    (net (code "50") (name "Net-(LIVE-PadA)") (class "Default")
      (node (ref "LIVE") (pin "A") (pinfunction "A_A") (pintype "passive"))
      (node (ref "R2") (pin "1") (pinfunction "1_1") (pintype "passive"))
    )
    (net (code "51") (name "Net-(NET-PadA)") (class "Default")
      (node (ref "NET") (pin "A") (pinfunction "A_A") (pintype "passive"))
      (node (ref "R9") (pin "1") (pinfunction "1_1") (pintype "passive"))
    )
    (net (code "52") (name "Net-(Q3-D)") (class "Default")
      (node (ref "JCS") (pin "1") (pinfunction "1_1") (pintype "passive"))
      (node (ref "Q3") (pin "1") (pinfunction "D_1") (pintype "passive"))
      (node (ref "R19") (pin "1") (pinfunction "1_1") (pintype "passive"))
      (node (ref "R44") (pin "1") (pinfunction "1_1") (pintype "passive"))
      (node (ref "SD2") (pin "2") (pinfunction "CD/DAT3(~{CS})_2") (pintype "bidirectional"))
    )
    (net (code "53") (name "Net-(Q3-G)") (class "Default")
      (node (ref "Q3") (pin "2") (pinfunction "G_2") (pintype "passive"))
      (node (ref "Q5") (pin "2") (pinfunction "G_2") (pintype "passive"))
      (node (ref "Q6") (pin "2") (pinfunction "G_2") (pintype "passive"))
      (node (ref "R42(0)") (pin "1") (pinfunction "1_1") (pintype "passive"))
    )
    (net (code "54") (name "Net-(Q5-D)") (class "Default")
      (node (ref "JSCK") (pin "1") (pinfunction "1_1") (pintype "passive"))
      (node (ref "Q5") (pin "1") (pinfunction "D_1") (pintype "passive"))
      (node (ref "R21") (pin "1") (pinfunction "1_1") (pintype "passive"))
      (node (ref "R36") (pin "1") (pinfunction "1_1") (pintype "passive"))
      (node (ref "SD2") (pin "5") (pinfunction "CLK(SCLK)_5") (pintype "input"))
    )
    (net (code "55") (name "Net-(Q6-D)") (class "Default")
      (node (ref "JMOSI") (pin "1") (pinfunction "1_1") (pintype "passive"))
      (node (ref "Q6") (pin "1") (pinfunction "D_1") (pintype "passive"))
      (node (ref "R22") (pin "1") (pinfunction "1_1") (pintype "passive"))
      (node (ref "R42") (pin "1") (pinfunction "1_1") (pintype "passive"))
      (node (ref "SD2") (pin "3") (pinfunction "CMD(DI)_3") (pintype "bidirectional"))
    )
    (net (code "56") (name "Net-(R8-Pad1)") (class "Default")
      (node (ref "R8") (pin "1") (pinfunction "1_1") (pintype "passive"))
      (node (ref "T5") (pin "B") (pinfunction "B_B") (pintype "passive"))
    )
    (net (code "57") (name "Net-(R25-Pad1)") (class "Default")
      (node (ref "R25") (pin "1") (pinfunction "1_1") (pintype "passive"))
      (node (ref "R26") (pin "2") (pinfunction "2_2") (pintype "passive"))
      (node (ref "R37") (pin "2") (pinfunction "2_2") (pintype "passive"))
      (node (ref "R51") (pin "1") (pinfunction "1_1") (pintype "passive"))
      (node (ref "R52") (pin "1") (pinfunction "1_1") (pintype "passive"))
      (node (ref "R53") (pin "1") (pinfunction "1_1") (pintype "passive"))
      (node (ref "R54") (pin "2") (pinfunction "2_2") (pintype "passive"))
      (node (ref "R55") (pin "2") (pinfunction "2_2") (pintype "passive"))
      (node (ref "R56") (pin "2") (pinfunction "2_2") (pintype "passive"))
    )
    (net (code "58") (name "Net-(R35-Pad1)") (class "Default")
      (node (ref "R35") (pin "1") (pinfunction "1_1") (pintype "passive"))
      (node (ref "R8") (pin "2") (pinfunction "2_2") (pintype "passive"))
    )
    (net (code "59") (name "Net-(SD2-DAT0(DO))") (class "Default")
      (node (ref "JMISO") (pin "1") (pinfunction "1_1") (pintype "passive"))
      (node (ref "R43") (pin "1") (pinfunction "1_1") (pintype "passive"))
      (node (ref "R47") (pin "1") (pinfunction "1_1") (pintype "passive"))
      (node (ref "R59") (pin "1") (pinfunction "1_1") (pintype "passive"))
      (node (ref "R59") (pin "2") (pinfunction "2_2") (pintype "passive"))
      (node (ref "SD2") (pin "7") (pinfunction "DAT0(DO)_7") (pintype "bidirectional"))
    )
    (net (code "60") (name "Net-(X1A-KL)") (class "Default")
      (node (ref "D1") (pin "A") (pinfunction "A_A") (pintype "passive"))
      (node (ref "J2") (pin "2") (pinfunction "2_2") (pintype "passive"))
      (node (ref "X1") (pin "1") (pinfunction "KL_1") (pintype "passive"))
    )
    (net (code "61") (name "Net-(X1D-KL)") (class "Default")
      (node (ref "J2") (pin "1") (pinfunction "1_1") (pintype "passive"))
      (node (ref "R25") (pin "2") (pinfunction "2_2") (pintype "passive"))
      (node (ref "R51") (pin "2") (pinfunction "2_2") (pintype "passive"))
      (node (ref "R52") (pin "2") (pinfunction "2_2") (pintype "passive"))
      (node (ref "R53") (pin "2") (pinfunction "2_2") (pintype "passive"))
      (node (ref "X1") (pin "3") (pinfunction "KL_3") (pintype "passive"))
    )
    (net (code "62") (name "Net-(X8-Pad4)") (class "Default")
      (node (ref "X8") (pin "4") (pinfunction "4_4") (pintype "passive"))
      (node (ref "X8") (pin "5") (pinfunction "5_5") (pintype "passive"))
    )
    (net (code "63") (name "RCK") (class "Default")
      (node (ref "IC1") (pin "12") (pinfunction "RCK_12") (pintype "input"))
      (node (ref "IC7") (pin "12") (pinfunction "(PCI22/AIN0OC0A)PD6_12") (pintype "bidirectional"))
    )
    (net (code "64") (name "RELAY_485") (class "Default")
      (node (ref "IC1") (pin "3") (pinfunction "QD_3") (pintype "tri_state"))
      (node (ref "R16") (pin "1") (pinfunction "1_1") (pintype "passive"))
    )
    (net (code "65") (name "RST") (class "Default")
      (node (ref "IC7") (pin "1") (pinfunction "PC6(/RESET/PCI14)_1") (pintype "bidirectional"))
      (node (ref "JP2") (pin "1") (pinfunction "1_1") (pintype "passive"))
      (node (ref "JP2") (pin "2") (pinfunction "2_2") (pintype "passive"))
      (node (ref "JP8") (pin "5") (pinfunction "5_5") (pintype "passive"))
      (node (ref "R6") (pin "1") (pinfunction "1_1") (pintype "passive"))
    )
    (net (code "66") (name "RX1") (class "Default")
      (node (ref "IC12") (pin "1") (pinfunction "RO_1") (pintype "output"))
      (node (ref "IC7") (pin "15") (pinfunction "(PCI1/OC1A/OC1S)PB1_15") (pintype "bidirectional"))
      (node (ref "R3") (pin "2") (pinfunction "2_2") (pintype "passive"))
    )
    (net (code "67") (name "RX2") (class "Default")
      (node (ref "IC7") (pin "5") (pinfunction "(PCI19/INT1/OC2B)PD3_5") (pintype "bidirectional"))
      (node (ref "R41") (pin "1") (pinfunction "1_1") (pintype "passive"))
    )
    (net (code "68") (name "RXD") (class "Default")
      (node (ref "IC7") (pin "2") (pinfunction "(PCI16/RXD)PD0_2") (pintype "bidirectional"))
      (node (ref "JP2") (pin "4") (pinfunction "4_4") (pintype "passive"))
      (node (ref "JP8") (pin "2") (pinfunction "2_2") (pintype "passive"))
    )
    (net (code "69") (name "SCK") (class "Default")
      (node (ref "IC7") (pin "19") (pinfunction "(PCI5/SCK)PB5_19") (pintype "bidirectional"))
      (node (ref "J8") (pin "3") (pinfunction "3_3") (pintype "passive"))
      (node (ref "Q5") (pin "3") (pinfunction "S_3") (pintype "passive"))
      (node (ref "R58") (pin "1") (pinfunction "1_1") (pintype "passive"))
      (node (ref "R58") (pin "2") (pinfunction "2_2") (pintype "passive"))
    )
    (net (code "70") (name "SCK2") (class "Default")
      (node (ref "IC1") (pin "11") (pinfunction "SCK_11") (pintype "input"))
      (node (ref "IC7") (pin "11") (pinfunction "(PCI21/T1/OC0B)PD5_11") (pintype "bidirectional"))
    )
    (net (code "71") (name "SCL") (class "Default")
      (node (ref "IC10") (pin "6") (pinfunction "SCL_6") (pintype "bidirectional"))
      (node (ref "IC7") (pin "28") (pinfunction "(PCI13/ADC5/SCL)PC5_28") (pintype "bidirectional"))
      (node (ref "R28") (pin "2") (pinfunction "2_2") (pintype "passive"))
    )
    (net (code "72") (name "SDA") (class "Default")
      (node (ref "IC10") (pin "5") (pinfunction "SDA_5") (pintype "bidirectional"))
      (node (ref "IC7") (pin "27") (pinfunction "(PCI12/ADC4/SDA)PC4_27") (pintype "bidirectional"))
      (node (ref "R29") (pin "1") (pinfunction "1_1") (pintype "passive"))
    )
    (net (code "73") (name "SD_CS") (class "Default")
      (node (ref "IC7") (pin "16") (pinfunction "(PCI2/SS/OC1B)PB2_16") (pintype "bidirectional"))
      (node (ref "Q3") (pin "3") (pinfunction "S_3") (pintype "passive"))
      (node (ref "R48") (pin "1") (pinfunction "1_1") (pintype "passive"))
      (node (ref "R48") (pin "2") (pinfunction "2_2") (pintype "passive"))
    )
    (net (code "74") (name "SER") (class "Default")
      (node (ref "IC1") (pin "14") (pinfunction "SER_14") (pintype "input"))
      (node (ref "IC7") (pin "13") (pinfunction "(PCI23/AIN1)PD7_13") (pintype "bidirectional"))
    )
    (net (code "75") (name "SIM_POW") (class "Default")
      (node (ref "C20") (pin "+") (pinfunction "+_+") (pintype "passive"))
      (node (ref "C22") (pin "1") (pinfunction "1_1") (pintype "passive"))
      (node (ref "C25") (pin "+") (pinfunction "+_+") (pintype "passive"))
      (node (ref "C8") (pin "+") (pinfunction "+_+") (pintype "passive"))
      (node (ref "D4") (pin "C") (pinfunction "C_C") (pintype "passive"))
      (node (ref "J14") (pin "1") (pinfunction "1_1") (pintype "passive"))
      (node (ref "JP1") (pin "1") (pinfunction "1_1") (pintype "passive"))
      (node (ref "JP3") (pin "1") (pinfunction "1_1") (pintype "passive"))
      (node (ref "L3") (pin "1") (pinfunction "1_1") (pintype "passive"))
      (node (ref "R4") (pin "2") (pinfunction "2_2") (pintype "passive"))
    )
    (net (code "76") (name "SQW") (class "Default")
      (node (ref "IC10") (pin "7") (pinfunction "SQW/OUT_7") (pintype "bidirectional"))
    )
    (net (code "77") (name "TX1") (class "Default")
      (node (ref "IC12") (pin "4") (pinfunction "DI_4") (pintype "input"))
      (node (ref "IC7") (pin "14") (pinfunction "(PCI0/ICP/CLKO)PB0_14") (pintype "bidirectional"))
      (node (ref "R20") (pin "2") (pinfunction "2_2") (pintype "passive"))
    )
    (net (code "78") (name "TX2") (class "Default")
      (node (ref "IC7") (pin "6") (pinfunction "(PCI20/XCK/T0)PD4_6") (pintype "bidirectional"))
      (node (ref "R40") (pin "1") (pinfunction "1_1") (pintype "passive"))
    )
    (net (code "79") (name "TXD") (class "Default")
      (node (ref "IC7") (pin "3") (pinfunction "(PCI17/TXD)PD1_3") (pintype "bidirectional"))
      (node (ref "JP2") (pin "6") (pinfunction "6_6") (pintype "passive"))
      (node (ref "JP8") (pin "1") (pinfunction "1_1") (pintype "passive"))
    )
    (net (code "80") (name "VCC") (class "Default")
      (node (ref "BUZ") (pin "+") (pinfunction "+_+") (pintype "passive"))
      (node (ref "C12") (pin "2") (pinfunction "2_2") (pintype "passive"))
      (node (ref "C14") (pin "2") (pinfunction "2_2") (pintype "passive"))
      (node (ref "C16") (pin "2") (pinfunction "2_2") (pintype "passive"))
      (node (ref "C18") (pin "+") (pinfunction "+_+") (pintype "passive"))
      (node (ref "C21") (pin "2") (pinfunction "2_2") (pintype "passive"))
      (node (ref "C3") (pin "+") (pinfunction "+_+") (pintype "passive"))
      (node (ref "C30") (pin "2") (pinfunction "2_2") (pintype "passive"))
      (node (ref "C31") (pin "+") (pinfunction "+_+") (pintype "passive"))
      (node (ref "C36") (pin "2") (pinfunction "2_2") (pintype "passive"))
      (node (ref "C6") (pin "2") (pinfunction "2_2") (pintype "passive"))
      (node (ref "D6") (pin "A") (pinfunction "A_A") (pintype "passive"))
      (node (ref "IC1") (pin "16") (pinfunction "VCC_16") (pintype "power_in"))
      (node (ref "IC10") (pin "8") (pinfunction "VCC_8") (pintype "power_in"))
      (node (ref "IC12") (pin "8") (pinfunction "VCC_8") (pintype "input"))
      (node (ref "IC2") (pin "3") (pinfunction "VO_3") (pintype "passive"))
      (node (ref "IC7") (pin "7") (pinfunction "VCC_7") (pintype "bidirectional"))
      (node (ref "IC9") (pin "8") (pinfunction "V+_8") (pintype "power_in"))
      (node (ref "JP1") (pin "8") (pinfunction "8_8") (pintype "passive"))
      (node (ref "JP2") (pin "3") (pinfunction "3_3") (pintype "passive"))
      (node (ref "JP3") (pin "8") (pinfunction "8_8") (pintype "passive"))
      (node (ref "JP6") (pin "6") (pinfunction "6_6") (pintype "passive"))
      (node (ref "JP7") (pin "6") (pinfunction "6_6") (pintype "passive"))
      (node (ref "JP8") (pin "4") (pinfunction "4_4") (pintype "passive"))
      (node (ref "L1") (pin "1") (pinfunction "1_1") (pintype "passive"))
      (node (ref "R10") (pin "2") (pinfunction "2_2") (pintype "passive"))
      (node (ref "R20") (pin "1") (pinfunction "1_1") (pintype "passive"))
      (node (ref "R28") (pin "1") (pinfunction "1_1") (pintype "passive"))
      (node (ref "R29") (pin "2") (pinfunction "2_2") (pintype "passive"))
      (node (ref "R3") (pin "1") (pinfunction "1_1") (pintype "passive"))
      (node (ref "R32") (pin "1") (pinfunction "1_1") (pintype "passive"))
      (node (ref "R34") (pin "1") (pinfunction "1_1") (pintype "passive"))
      (node (ref "R44(0)") (pin "2") (pinfunction "2_2") (pintype "passive"))
      (node (ref "R46") (pin "1") (pinfunction "1_1") (pintype "passive"))
      (node (ref "R48(0)") (pin "2") (pinfunction "2_2") (pintype "passive"))
      (node (ref "R6") (pin "2") (pinfunction "2_2") (pintype "passive"))
      (node (ref "R60") (pin "2") (pinfunction "2_2") (pintype "passive"))
      (node (ref "SETUP") (pin "3") (pinfunction "P_3") (pintype "passive"))
      (node (ref "SETUP") (pin "4") (pinfunction "P1_4") (pintype "passive"))
    )
    (net (code "81") (name "unconnected-(IC1A-QH*-Pad9)") (class "Default")
      (node (ref "IC1") (pin "9") (pinfunction "QH*_9") (pintype "tri_state"))
    )
    (net (code "82") (name "unconnected-(JP1-Pad6)") (class "Default")
      (node (ref "JP1") (pin "6") (pinfunction "6_6") (pintype "passive"))
    )
    (net (code "83") (name "unconnected-(JP3-Pad6)") (class "Default")
      (node (ref "JP3") (pin "6") (pinfunction "6_6") (pintype "passive"))
    )
    (net (code "84") (name "unconnected-(POW-PadA)") (class "Default")
      (node (ref "POW") (pin "A") (pinfunction "A_A") (pintype "passive"))
    )
    (net (code "85") (name "unconnected-(R12-Pad1)") (class "Default")
      (node (ref "R12") (pin "1") (pinfunction "1_1") (pintype "passive"))
    )
    (net (code "86") (name "unconnected-(R12-Pad2)") (class "Default")
      (node (ref "R12") (pin "2") (pinfunction "2_2") (pintype "passive"))
    )
    (net (code "87") (name "unconnected-(R16-Pad2)") (class "Default")
      (node (ref "R16") (pin "2") (pinfunction "2_2") (pintype "passive"))
    )
    (net (code "88") (name "unconnected-(SD2-DAT1-Pad8)") (class "Default")
      (node (ref "SD2") (pin "8") (pinfunction "DAT1_8") (pintype "bidirectional"))
    )
    (net (code "89") (name "unconnected-(SD2-DAT2-Pad1)") (class "Default")
      (node (ref "SD2") (pin "1") (pinfunction "DAT2_1") (pintype "bidirectional"))
    )
    (net (code "90") (name "unconnected-(SD2-~{CARD}-Pad9)") (class "Default")
      (node (ref "SD2") (pin "9") (pinfunction "~{CARD}_9") (pintype "passive"))
    )
    (net (code "91") (name "unconnected-(U$1-PadDTR)") (class "Default")
      (node (ref "U$1") (pin "DTR") (pinfunction "DTR_DTR") (pintype "bidirectional"))
    )
    (net (code "92") (name "unconnected-(U$1-PadGND)") (class "Default")
      (node (ref "U$1") (pin "GND") (pinfunction "GND_GND") (pintype "bidirectional"))
    )
    (net (code "93") (name "unconnected-(U$1-PadMIC+)") (class "Default")
      (node (ref "U$1") (pin "MIC+") (pinfunction "MIC+_MIC+") (pintype "bidirectional"))
    )
    (net (code "94") (name "unconnected-(U$1-PadMIC-)") (class "Default")
      (node (ref "U$1") (pin "MIC-") (pinfunction "MIC-_MIC-") (pintype "bidirectional"))
    )
    (net (code "95") (name "unconnected-(U$1-PadNET)") (class "Default")
      (node (ref "U$1") (pin "NET") (pinfunction "NET_NET") (pintype "bidirectional"))
    )
    (net (code "96") (name "unconnected-(U$1-PadRING)") (class "Default")
      (node (ref "U$1") (pin "RING") (pinfunction "RING_RING") (pintype "bidirectional"))
    )
    (net (code "97") (name "unconnected-(U$1-PadRST)") (class "Default")
      (node (ref "U$1") (pin "RST") (pinfunction "RST_RST") (pintype "bidirectional"))
    )
    (net (code "98") (name "unconnected-(U$1-PadRX)") (class "Default")
      (node (ref "U$1") (pin "RX") (pinfunction "RX_RX") (pintype "bidirectional"))
    )
    (net (code "99") (name "unconnected-(U$1-PadSPK+)") (class "Default")
      (node (ref "U$1") (pin "SPK+") (pinfunction "SPK+_SPK+") (pintype "bidirectional"))
    )
    (net (code "100") (name "unconnected-(U$1-PadSPK-)") (class "Default")
      (node (ref "U$1") (pin "SPK-") (pinfunction "SPK-_SPK-") (pintype "bidirectional"))
    )
    (net (code "101") (name "unconnected-(U$1-PadTX)") (class "Default")
      (node (ref "U$1") (pin "TX") (pinfunction "TX_TX") (pintype "bidirectional"))
    )
    (net (code "102") (name "unconnected-(U$1-PadVCC)") (class "Default")
      (node (ref "U$1") (pin "VCC") (pinfunction "VCC_VCC") (pintype "bidirectional"))
    )
  )
)
